# electricals_with_iPod_v2.net
KiCad netlist of a schematic drawn in EAGLE
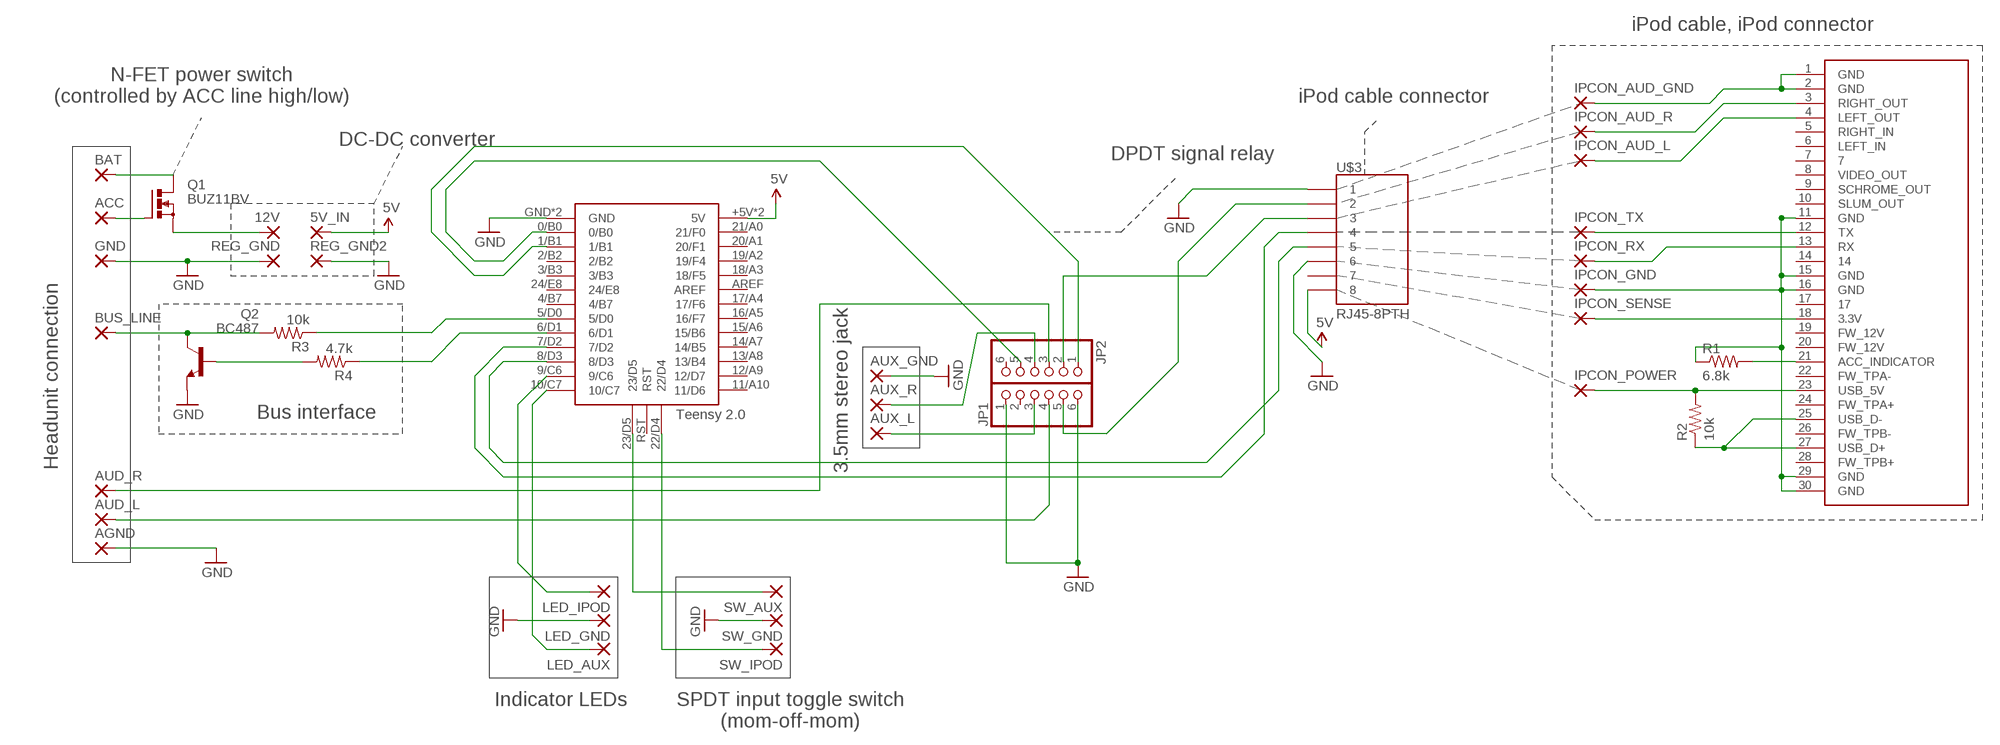
[diagram p0: schematic, sheet 1]

(export (version "E")
  (design (tool "Eeschema 10.0.6"))
  (components
    (comp (ref "5V_IN")
      (value "2,54/1,1")
      (footprint "eagle-import:2,54_1,1")
      (libsource (lib "eagle-import") (part "2,54/1,1"))
    )
    (comp (ref "12V")
      (value "2,54/1,1")
      (footprint "eagle-import:2,54_1,1")
      (libsource (lib "eagle-import") (part "2,54/1,1"))
    )
    (comp (ref "ACC")
      (value "1,6/0,9")
      (footprint "eagle-import:1,6_0,9")
      (libsource (lib "eagle-import") (part "1,6/0,9"))
    )
    (comp (ref "AGND")
      (value "1,6/0,9")
      (footprint "eagle-import:1,6_0,9")
      (libsource (lib "eagle-import") (part "1,6/0,9"))
    )
    (comp (ref "AUD_L")
      (value "1,6/0,9")
      (footprint "eagle-import:1,6_0,9")
      (libsource (lib "eagle-import") (part "1,6/0,9"))
    )
    (comp (ref "AUD_R")
      (value "1,6/0,9")
      (footprint "eagle-import:1,6_0,9")
      (libsource (lib "eagle-import") (part "1,6/0,9"))
    )
    (comp (ref "AUX_GND")
      (value "1,6/0,9")
      (footprint "eagle-import:1,6_0,9")
      (libsource (lib "eagle-import") (part "1,6/0,9"))
    )
    (comp (ref "AUX_L")
      (value "1,6/0,9")
      (footprint "eagle-import:1,6_0,9")
      (libsource (lib "eagle-import") (part "1,6/0,9"))
    )
    (comp (ref "AUX_R")
      (value "1,6/0,9")
      (footprint "eagle-import:1,6_0,9")
      (libsource (lib "eagle-import") (part "1,6/0,9"))
    )
    (comp (ref "BAT")
      (value "2,54/1,1")
      (footprint "eagle-import:2,54_1,1")
      (libsource (lib "eagle-import") (part "2,54/1,1"))
    )
    (comp (ref "BUS_LINE")
      (value "1,6/0,9")
      (footprint "eagle-import:1,6_0,9")
      (libsource (lib "eagle-import") (part "1,6/0,9"))
    )
    (comp (ref "GND")
      (value "2,54/1,1")
      (footprint "eagle-import:2,54_1,1")
      (libsource (lib "eagle-import") (part "2,54/1,1"))
    )
    (comp (ref "IPCON_AUD_GND")
      (value "1,6/0,9")
      (footprint "eagle-import:1,6_0,9")
      (libsource (lib "eagle-import") (part "1,6/0,9"))
    )
    (comp (ref "IPCON_AUD_L")
      (value "1,6/0,9")
      (footprint "eagle-import:1,6_0,9")
      (libsource (lib "eagle-import") (part "1,6/0,9"))
    )
    (comp (ref "IPCON_AUD_R")
      (value "1,6/0,9")
      (footprint "eagle-import:1,6_0,9")
      (libsource (lib "eagle-import") (part "1,6/0,9"))
    )
    (comp (ref "IPCON_GND")
      (value "1,6/0,9")
      (footprint "eagle-import:1,6_0,9")
      (libsource (lib "eagle-import") (part "1,6/0,9"))
    )
    (comp (ref "IPCON_POWER")
      (value "1,6/0,9")
      (footprint "eagle-import:1,6_0,9")
      (libsource (lib "eagle-import") (part "1,6/0,9"))
    )
    (comp (ref "IPCON_RX")
      (value "1,6/0,9")
      (footprint "eagle-import:1,6_0,9")
      (libsource (lib "eagle-import") (part "1,6/0,9"))
    )
    (comp (ref "IPCON_SENSE")
      (value "1,6/0,9")
      (footprint "eagle-import:1,6_0,9")
      (libsource (lib "eagle-import") (part "1,6/0,9"))
    )
    (comp (ref "IPCON_TX")
      (value "1,6/0,9")
      (footprint "eagle-import:1,6_0,9")
      (libsource (lib "eagle-import") (part "1,6/0,9"))
    )
    (comp (ref "JP1")
      (value "PINHD-1X6")
      (footprint "eagle-import:1X06")
      (libsource (lib "eagle-import") (part "PINHD-1X6"))
    )
    (comp (ref "JP2")
      (value "PINHD-1X6")
      (footprint "eagle-import:1X06")
      (libsource (lib "eagle-import") (part "PINHD-1X6"))
    )
    (comp (ref "LED_AUX")
      (value "1,6/0,9")
      (footprint "eagle-import:1,6_0,9")
      (libsource (lib "eagle-import") (part "1,6/0,9"))
    )
    (comp (ref "LED_GND")
      (value "1,6/0,9")
      (footprint "eagle-import:1,6_0,9")
      (libsource (lib "eagle-import") (part "1,6/0,9"))
    )
    (comp (ref "LED_IPOD")
      (value "1,6/0,9")
      (footprint "eagle-import:1,6_0,9")
      (libsource (lib "eagle-import") (part "1,6/0,9"))
    )
    (comp (ref "Q1")
      (value "BUZ11BV")
      (footprint "eagle-import:TO220BV")
      (libsource (lib "eagle-import") (part "BUZ11BV"))
    )
    (comp (ref "Q2")
      (value "BC487")
      (footprint "eagle-import:TO92-EBC")
      (libsource (lib "eagle-import") (part "BC487"))
    )
    (comp (ref "R1")
      (value "6.8k")
      (footprint "eagle-import:1206")
      (libsource (lib "eagle-import") (part "RESISTOR1206"))
    )
    (comp (ref "R2")
      (value "10k")
      (footprint "eagle-import:1206")
      (libsource (lib "eagle-import") (part "RESISTOR1206"))
    )
    (comp (ref "R3")
      (value "10k")
      (footprint "eagle-import:1206")
      (libsource (lib "eagle-import") (part "RESISTOR1206"))
    )
    (comp (ref "R4")
      (value "4.7k")
      (footprint "eagle-import:1206")
      (libsource (lib "eagle-import") (part "RESISTOR1206"))
    )
    (comp (ref "REG_GND")
      (value "2,54/1,1")
      (footprint "eagle-import:2,54_1,1")
      (libsource (lib "eagle-import") (part "2,54/1,1"))
    )
    (comp (ref "REG_GND2")
      (value "2,54/1,1")
      (footprint "eagle-import:2,54_1,1")
      (libsource (lib "eagle-import") (part "2,54/1,1"))
    )
    (comp (ref "SW_AUX")
      (value "1,6/0,9")
      (footprint "eagle-import:1,6_0,9")
      (libsource (lib "eagle-import") (part "1,6/0,9"))
    )
    (comp (ref "SW_GND")
      (value "1,6/0,9")
      (footprint "eagle-import:1,6_0,9")
      (libsource (lib "eagle-import") (part "1,6/0,9"))
    )
    (comp (ref "SW_IPOD")
      (value "1,6/0,9")
      (footprint "eagle-import:1,6_0,9")
      (libsource (lib "eagle-import") (part "1,6/0,9"))
    )
    (comp (ref "U$1")
      (value "IPOD_CONNECTOR_MALE")
      (footprint "eagle-import:IPOD_MALE_CONNECTOR")
      (libsource (lib "eagle-import") (part "IPOD_CONNECTOR_MALE"))
    )
    (comp (ref "U$3")
      (value "RJ45-8PTH")
      (footprint "eagle-import:RJ45-8")
      (libsource (lib "eagle-import") (part "RJ45-8PTH"))
    )
    (comp (ref "U$5")
      (value "TEENSY-2.0")
      (footprint "eagle-import:TEENSY_2.0")
      (libsource (lib "eagle-import") (part "TEENSY-2.0"))
    )
  )
  (nets
    (net (code "1") (name "5V") (class "Default")
      (node (ref "5V_IN") (pin "1") (pinfunction "P_1") (pintype "passive"))
      (node (ref "U$3") (pin "8") (pinfunction "8_8") (pintype "bidirectional"))
      (node (ref "U$5") (pin "+5V") (pinfunction "5V_+5V") (pintype "bidirectional"))
      (node (ref "U$5") (pin "+5V_") (pinfunction "5V_+5V_") (pintype "bidirectional"))
    )
    (net (code "2") (name "GND") (class "Default")
      (node (ref "AGND") (pin "1") (pinfunction "P_1") (pintype "passive"))
      (node (ref "AUX_GND") (pin "1") (pinfunction "P_1") (pintype "passive"))
      (node (ref "GND") (pin "1") (pinfunction "P_1") (pintype "passive"))
      (node (ref "JP1") (pin "1") (pinfunction "1_1") (pintype "passive"))
      (node (ref "JP1") (pin "6") (pinfunction "6_6") (pintype "passive"))
      (node (ref "LED_GND") (pin "1") (pinfunction "P_1") (pintype "passive"))
      (node (ref "Q2") (pin "E") (pinfunction "E_E") (pintype "passive"))
      (node (ref "REG_GND") (pin "1") (pinfunction "P_1") (pintype "passive"))
      (node (ref "REG_GND2") (pin "1") (pinfunction "P_1") (pintype "passive"))
      (node (ref "SW_GND") (pin "1") (pinfunction "P_1") (pintype "passive"))
      (node (ref "U$3") (pin "1") (pinfunction "1_1") (pintype "bidirectional"))
      (node (ref "U$3") (pin "6") (pinfunction "6_6") (pintype "bidirectional"))
      (node (ref "U$5") (pin "GND") (pinfunction "GND_GND") (pintype "bidirectional"))
      (node (ref "U$5") (pin "GND_") (pinfunction "GND_GND_") (pintype "bidirectional"))
    )
    (net (code "3") (name "Net-(12V-P)") (class "Default")
      (node (ref "12V") (pin "1") (pinfunction "P_1") (pintype "passive"))
      (node (ref "Q1") (pin "S") (pinfunction "S_S") (pintype "passive"))
    )
    (net (code "4") (name "Net-(ACC-P)") (class "Default")
      (node (ref "ACC") (pin "1") (pinfunction "P_1") (pintype "passive"))
      (node (ref "Q1") (pin "G") (pinfunction "G_G") (pintype "passive"))
    )
    (net (code "5") (name "Net-(AUD_L-P)") (class "Default")
      (node (ref "AUD_L") (pin "1") (pinfunction "P_1") (pintype "passive"))
      (node (ref "JP1") (pin "4") (pinfunction "4_4") (pintype "passive"))
    )
    (net (code "6") (name "Net-(AUD_R-P)") (class "Default")
      (node (ref "AUD_R") (pin "1") (pinfunction "P_1") (pintype "passive"))
      (node (ref "JP2") (pin "3") (pinfunction "3_3") (pintype "passive"))
    )
    (net (code "7") (name "Net-(AUX_L-P)") (class "Default")
      (node (ref "AUX_L") (pin "1") (pinfunction "P_1") (pintype "passive"))
      (node (ref "JP1") (pin "3") (pinfunction "3_3") (pintype "passive"))
    )
    (net (code "8") (name "Net-(AUX_R-P)") (class "Default")
      (node (ref "AUX_R") (pin "1") (pinfunction "P_1") (pintype "passive"))
      (node (ref "JP2") (pin "4") (pinfunction "4_4") (pintype "passive"))
    )
    (net (code "9") (name "Net-(BAT-P)") (class "Default")
      (node (ref "BAT") (pin "1") (pinfunction "P_1") (pintype "passive"))
      (node (ref "Q1") (pin "D") (pinfunction "D_D") (pintype "passive"))
    )
    (net (code "10") (name "Net-(BUS_LINE-P)") (class "Default")
      (node (ref "BUS_LINE") (pin "1") (pinfunction "P_1") (pintype "passive"))
      (node (ref "Q2") (pin "C") (pinfunction "C_C") (pintype "passive"))
      (node (ref "R3") (pin "2") (pinfunction "2_2") (pintype "passive"))
    )
    (net (code "11") (name "Net-(IPCON_AUD_GND-P)") (class "Default")
      (node (ref "IPCON_AUD_GND") (pin "1") (pinfunction "P_1") (pintype "passive"))
      (node (ref "U$1") (pin "1") (pinfunction "GND_1") (pintype "bidirectional"))
      (node (ref "U$1") (pin "2") (pinfunction "GND_2") (pintype "bidirectional"))
    )
    (net (code "12") (name "Net-(IPCON_AUD_L-P)") (class "Default")
      (node (ref "IPCON_AUD_L") (pin "1") (pinfunction "P_1") (pintype "passive"))
      (node (ref "U$1") (pin "4") (pinfunction "LEFT_OUT_4") (pintype "bidirectional"))
    )
    (net (code "13") (name "Net-(IPCON_AUD_R-P)") (class "Default")
      (node (ref "IPCON_AUD_R") (pin "1") (pinfunction "P_1") (pintype "passive"))
      (node (ref "U$1") (pin "3") (pinfunction "RIGHT_OUT_3") (pintype "bidirectional"))
    )
    (net (code "14") (name "Net-(IPCON_GND-P)") (class "Default")
      (node (ref "IPCON_GND") (pin "1") (pinfunction "P_1") (pintype "passive"))
      (node (ref "R1") (pin "1") (pinfunction "1_1") (pintype "passive"))
      (node (ref "U$1") (pin "11") (pinfunction "GND_11") (pintype "bidirectional"))
      (node (ref "U$1") (pin "15") (pinfunction "GND_15") (pintype "bidirectional"))
      (node (ref "U$1") (pin "16") (pinfunction "GND_16") (pintype "bidirectional"))
      (node (ref "U$1") (pin "29") (pinfunction "GND_29") (pintype "bidirectional"))
      (node (ref "U$1") (pin "30") (pinfunction "GND_30") (pintype "bidirectional"))
    )
    (net (code "15") (name "Net-(IPCON_POWER-P)") (class "Default")
      (node (ref "IPCON_POWER") (pin "1") (pinfunction "P_1") (pintype "passive"))
      (node (ref "R2") (pin "2") (pinfunction "2_2") (pintype "passive"))
      (node (ref "U$1") (pin "23") (pinfunction "USB_5V_23") (pintype "bidirectional"))
    )
    (net (code "16") (name "Net-(IPCON_RX-P)") (class "Default")
      (node (ref "IPCON_RX") (pin "1") (pinfunction "P_1") (pintype "passive"))
      (node (ref "U$1") (pin "13") (pinfunction "RX_13") (pintype "bidirectional"))
    )
    (net (code "17") (name "Net-(IPCON_SENSE-P)") (class "Default")
      (node (ref "IPCON_SENSE") (pin "1") (pinfunction "P_1") (pintype "passive"))
      (node (ref "U$1") (pin "18") (pinfunction "3.3V_18") (pintype "bidirectional"))
    )
    (net (code "18") (name "Net-(IPCON_TX-P)") (class "Default")
      (node (ref "IPCON_TX") (pin "1") (pinfunction "P_1") (pintype "passive"))
      (node (ref "U$1") (pin "12") (pinfunction "TX_12") (pintype "bidirectional"))
    )
    (net (code "19") (name "Net-(JP1-Pad5)") (class "Default")
      (node (ref "JP1") (pin "5") (pinfunction "5_5") (pintype "passive"))
      (node (ref "U$3") (pin "2") (pinfunction "2_2") (pintype "bidirectional"))
    )
    (net (code "20") (name "Net-(JP2-Pad1)") (class "Default")
      (node (ref "JP2") (pin "1") (pinfunction "1_1") (pintype "passive"))
      (node (ref "U$5") (pin "1/B1") (pinfunction "1/B1_1/B1") (pintype "bidirectional"))
    )
    (net (code "21") (name "Net-(JP2-Pad2)") (class "Default")
      (node (ref "JP2") (pin "2") (pinfunction "2_2") (pintype "passive"))
      (node (ref "U$3") (pin "3") (pinfunction "3_3") (pintype "bidirectional"))
    )
    (net (code "22") (name "Net-(JP2-Pad5)") (class "Default")
      (node (ref "JP2") (pin "5") (pinfunction "5_5") (pintype "passive"))
      (node (ref "U$5") (pin "0/B0") (pinfunction "0/B0_0/B0") (pintype "bidirectional"))
    )
    (net (code "23") (name "Net-(LED_AUX-P)") (class "Default")
      (node (ref "LED_AUX") (pin "1") (pinfunction "P_1") (pintype "passive"))
      (node (ref "U$5") (pin "10/C7") (pinfunction "10/C7_10/C7") (pintype "bidirectional"))
    )
    (net (code "24") (name "Net-(LED_IPOD-P)") (class "Default")
      (node (ref "LED_IPOD") (pin "1") (pinfunction "P_1") (pintype "passive"))
      (node (ref "U$5") (pin "9/C6") (pinfunction "9/C6_9/C6") (pintype "bidirectional"))
    )
    (net (code "25") (name "Net-(Q2-PadB)") (class "Default")
      (node (ref "Q2") (pin "B") (pinfunction "B_B") (pintype "passive"))
      (node (ref "R4") (pin "2") (pinfunction "2_2") (pintype "passive"))
    )
    (net (code "26") (name "Net-(R3-Pad1)") (class "Default")
      (node (ref "R3") (pin "1") (pinfunction "1_1") (pintype "passive"))
      (node (ref "U$5") (pin "5/D0") (pinfunction "5/D0_5/D0") (pintype "bidirectional"))
    )
    (net (code "27") (name "Net-(R4-Pad1)") (class "Default")
      (node (ref "R4") (pin "1") (pinfunction "1_1") (pintype "passive"))
      (node (ref "U$5") (pin "6/D1") (pinfunction "6/D1_6/D1") (pintype "bidirectional"))
    )
    (net (code "28") (name "Net-(SW_AUX-P)") (class "Default")
      (node (ref "SW_AUX") (pin "1") (pinfunction "P_1") (pintype "passive"))
      (node (ref "U$5") (pin "23/D5") (pinfunction "23/D5_23/D5") (pintype "bidirectional"))
    )
    (net (code "29") (name "Net-(SW_IPOD-P)") (class "Default")
      (node (ref "SW_IPOD") (pin "1") (pinfunction "P_1") (pintype "passive"))
      (node (ref "U$5") (pin "22/D4") (pinfunction "22/D4_22/D4") (pintype "bidirectional"))
    )
    (net (code "30") (name "Net-(U$1-ACC_INDICATOR)") (class "Default")
      (node (ref "R1") (pin "2") (pinfunction "2_2") (pintype "passive"))
      (node (ref "U$1") (pin "21") (pinfunction "ACC_INDICATOR_21") (pintype "bidirectional"))
    )
    (net (code "31") (name "Net-(U$1-USB_D+)") (class "Default")
      (node (ref "R2") (pin "1") (pinfunction "1_1") (pintype "passive"))
      (node (ref "U$1") (pin "25") (pinfunction "USB_D-_25") (pintype "bidirectional"))
      (node (ref "U$1") (pin "27") (pinfunction "USB_D+_27") (pintype "bidirectional"))
    )
    (net (code "32") (name "Net-(U$3-Pad4)") (class "Default")
      (node (ref "U$3") (pin "4") (pinfunction "4_4") (pintype "bidirectional"))
      (node (ref "U$5") (pin "7/D2") (pinfunction "7/D2_7/D2") (pintype "bidirectional"))
    )
    (net (code "33") (name "Net-(U$3-Pad5)") (class "Default")
      (node (ref "U$3") (pin "5") (pinfunction "5_5") (pintype "bidirectional"))
      (node (ref "U$5") (pin "8/D3") (pinfunction "8/D3_8/D3") (pintype "bidirectional"))
    )
    (net (code "34") (name "unconnected-(JP1-Pad2)") (class "Default")
      (node (ref "JP1") (pin "2") (pinfunction "2_2") (pintype "passive"))
    )
    (net (code "35") (name "unconnected-(JP2-Pad6)") (class "Default")
      (node (ref "JP2") (pin "6") (pinfunction "6_6") (pintype "passive"))
    )
    (net (code "36") (name "unconnected-(U$1-FW_12V-Pad19)") (class "Default")
      (node (ref "U$1") (pin "19") (pinfunction "FW_12V_19") (pintype "bidirectional"))
    )
    (net (code "37") (name "unconnected-(U$1-FW_12V-Pad20)") (class "Default")
      (node (ref "U$1") (pin "20") (pinfunction "FW_12V_20") (pintype "bidirectional"))
    )
    (net (code "38") (name "unconnected-(U$1-FW_TPA+-Pad24)") (class "Default")
      (node (ref "U$1") (pin "24") (pinfunction "FW_TPA+_24") (pintype "bidirectional"))
    )
    (net (code "39") (name "unconnected-(U$1-FW_TPA--Pad22)") (class "Default")
      (node (ref "U$1") (pin "22") (pinfunction "FW_TPA-_22") (pintype "bidirectional"))
    )
    (net (code "40") (name "unconnected-(U$1-FW_TPB+-Pad28)") (class "Default")
      (node (ref "U$1") (pin "28") (pinfunction "FW_TPB+_28") (pintype "bidirectional"))
    )
    (net (code "41") (name "unconnected-(U$1-FW_TPB--Pad26)") (class "Default")
      (node (ref "U$1") (pin "26") (pinfunction "FW_TPB-_26") (pintype "bidirectional"))
    )
    (net (code "42") (name "unconnected-(U$1-LEFT_IN-Pad6)") (class "Default")
      (node (ref "U$1") (pin "6") (pinfunction "LEFT_IN_6") (pintype "bidirectional"))
    )
    (net (code "43") (name "unconnected-(U$1-Pad7)") (class "Default")
      (node (ref "U$1") (pin "7") (pinfunction "7_7") (pintype "bidirectional"))
    )
    (net (code "44") (name "unconnected-(U$1-Pad14)") (class "Default")
      (node (ref "U$1") (pin "14") (pinfunction "14_14") (pintype "bidirectional"))
    )
    (net (code "45") (name "unconnected-(U$1-Pad17)") (class "Default")
      (node (ref "U$1") (pin "17") (pinfunction "17_17") (pintype "bidirectional"))
    )
    (net (code "46") (name "unconnected-(U$1-RIGHT_IN-Pad5)") (class "Default")
      (node (ref "U$1") (pin "5") (pinfunction "RIGHT_IN_5") (pintype "bidirectional"))
    )
    (net (code "47") (name "unconnected-(U$1-SCHROME_OUT-Pad9)") (class "Default")
      (node (ref "U$1") (pin "9") (pinfunction "SCHROME_OUT_9") (pintype "bidirectional"))
    )
    (net (code "48") (name "unconnected-(U$1-SLUM_OUT-Pad10)") (class "Default")
      (node (ref "U$1") (pin "10") (pinfunction "SLUM_OUT_10") (pintype "bidirectional"))
    )
    (net (code "49") (name "unconnected-(U$1-VIDEO_OUT-Pad8)") (class "Default")
      (node (ref "U$1") (pin "8") (pinfunction "VIDEO_OUT_8") (pintype "bidirectional"))
    )
    (net (code "50") (name "unconnected-(U$3-Pad7)") (class "Default")
      (node (ref "U$3") (pin "7") (pinfunction "7_7") (pintype "bidirectional"))
    )
    (net (code "51") (name "unconnected-(U$5-11{slash}D6-Pad11{slash}A10)") (class "Default")
      (node (ref "U$5") (pin "11/A10") (pinfunction "11/D6_11/A10") (pintype "bidirectional"))
    )
    (net (code "52") (name "unconnected-(U$5-12{slash}D7-Pad12{slash}A9)") (class "Default")
      (node (ref "U$5") (pin "12/A9") (pinfunction "12/D7_12/A9") (pintype "bidirectional"))
    )
    (net (code "53") (name "unconnected-(U$5-13{slash}B4-Pad13{slash}A8)") (class "Default")
      (node (ref "U$5") (pin "13/A8") (pinfunction "13/B4_13/A8") (pintype "bidirectional"))
    )
    (net (code "54") (name "unconnected-(U$5-14{slash}B5-Pad14{slash}A7)") (class "Default")
      (node (ref "U$5") (pin "14/A7") (pinfunction "14/B5_14/A7") (pintype "bidirectional"))
    )
    (net (code "55") (name "unconnected-(U$5-15{slash}B6-Pad15{slash}A6)") (class "Default")
      (node (ref "U$5") (pin "15/A6") (pinfunction "15/B6_15/A6") (pintype "bidirectional"))
    )
    (net (code "56") (name "unconnected-(U$5-16{slash}F7-Pad16{slash}A5)") (class "Default")
      (node (ref "U$5") (pin "16/A5") (pinfunction "16/F7_16/A5") (pintype "bidirectional"))
    )
    (net (code "57") (name "unconnected-(U$5-17{slash}F6-Pad17{slash}A4)") (class "Default")
      (node (ref "U$5") (pin "17/A4") (pinfunction "17/F6_17/A4") (pintype "bidirectional"))
    )
    (net (code "58") (name "unconnected-(U$5-18{slash}F5-Pad18{slash}A3)") (class "Default")
      (node (ref "U$5") (pin "18/A3") (pinfunction "18/F5_18/A3") (pintype "bidirectional"))
    )
    (net (code "59") (name "unconnected-(U$5-19{slash}F4-Pad19{slash}A2)") (class "Default")
      (node (ref "U$5") (pin "19/A2") (pinfunction "19/F4_19/A2") (pintype "bidirectional"))
    )
    (net (code "60") (name "unconnected-(U$5-20{slash}F1-Pad20{slash}A1)") (class "Default")
      (node (ref "U$5") (pin "20/A1") (pinfunction "20/F1_20/A1") (pintype "bidirectional"))
    )
    (net (code "61") (name "unconnected-(U$5-21{slash}F0-Pad21{slash}A0)") (class "Default")
      (node (ref "U$5") (pin "21/A0") (pinfunction "21/F0_21/A0") (pintype "bidirectional"))
    )
    (net (code "62") (name "unconnected-(U$5-Pad2{slash}B2)") (class "Default")
      (node (ref "U$5") (pin "2/B2") (pinfunction "2/B2_2/B2") (pintype "bidirectional"))
    )
    (net (code "63") (name "unconnected-(U$5-Pad3{slash}B3)") (class "Default")
      (node (ref "U$5") (pin "3/B3") (pinfunction "3/B3_3/B3") (pintype "bidirectional"))
    )
    (net (code "64") (name "unconnected-(U$5-Pad4{slash}B7)") (class "Default")
      (node (ref "U$5") (pin "4/B7") (pinfunction "4/B7_4/B7") (pintype "bidirectional"))
    )
    (net (code "65") (name "unconnected-(U$5-Pad24{slash}E8)") (class "Default")
      (node (ref "U$5") (pin "24/E8") (pinfunction "24/E8_24/E8") (pintype "bidirectional"))
    )
    (net (code "66") (name "unconnected-(U$5-PadAREF)") (class "Default")
      (node (ref "U$5") (pin "AREF") (pinfunction "AREF_AREF") (pintype "bidirectional"))
    )
    (net (code "67") (name "unconnected-(U$5-PadRST)") (class "Default")
      (node (ref "U$5") (pin "RST") (pinfunction "RST_RST") (pintype "bidirectional"))
    )
  )
)
